# EasyArduino_2025-08-07.net
KiCad netlist of a schematic drawn in EasyEDA Pro
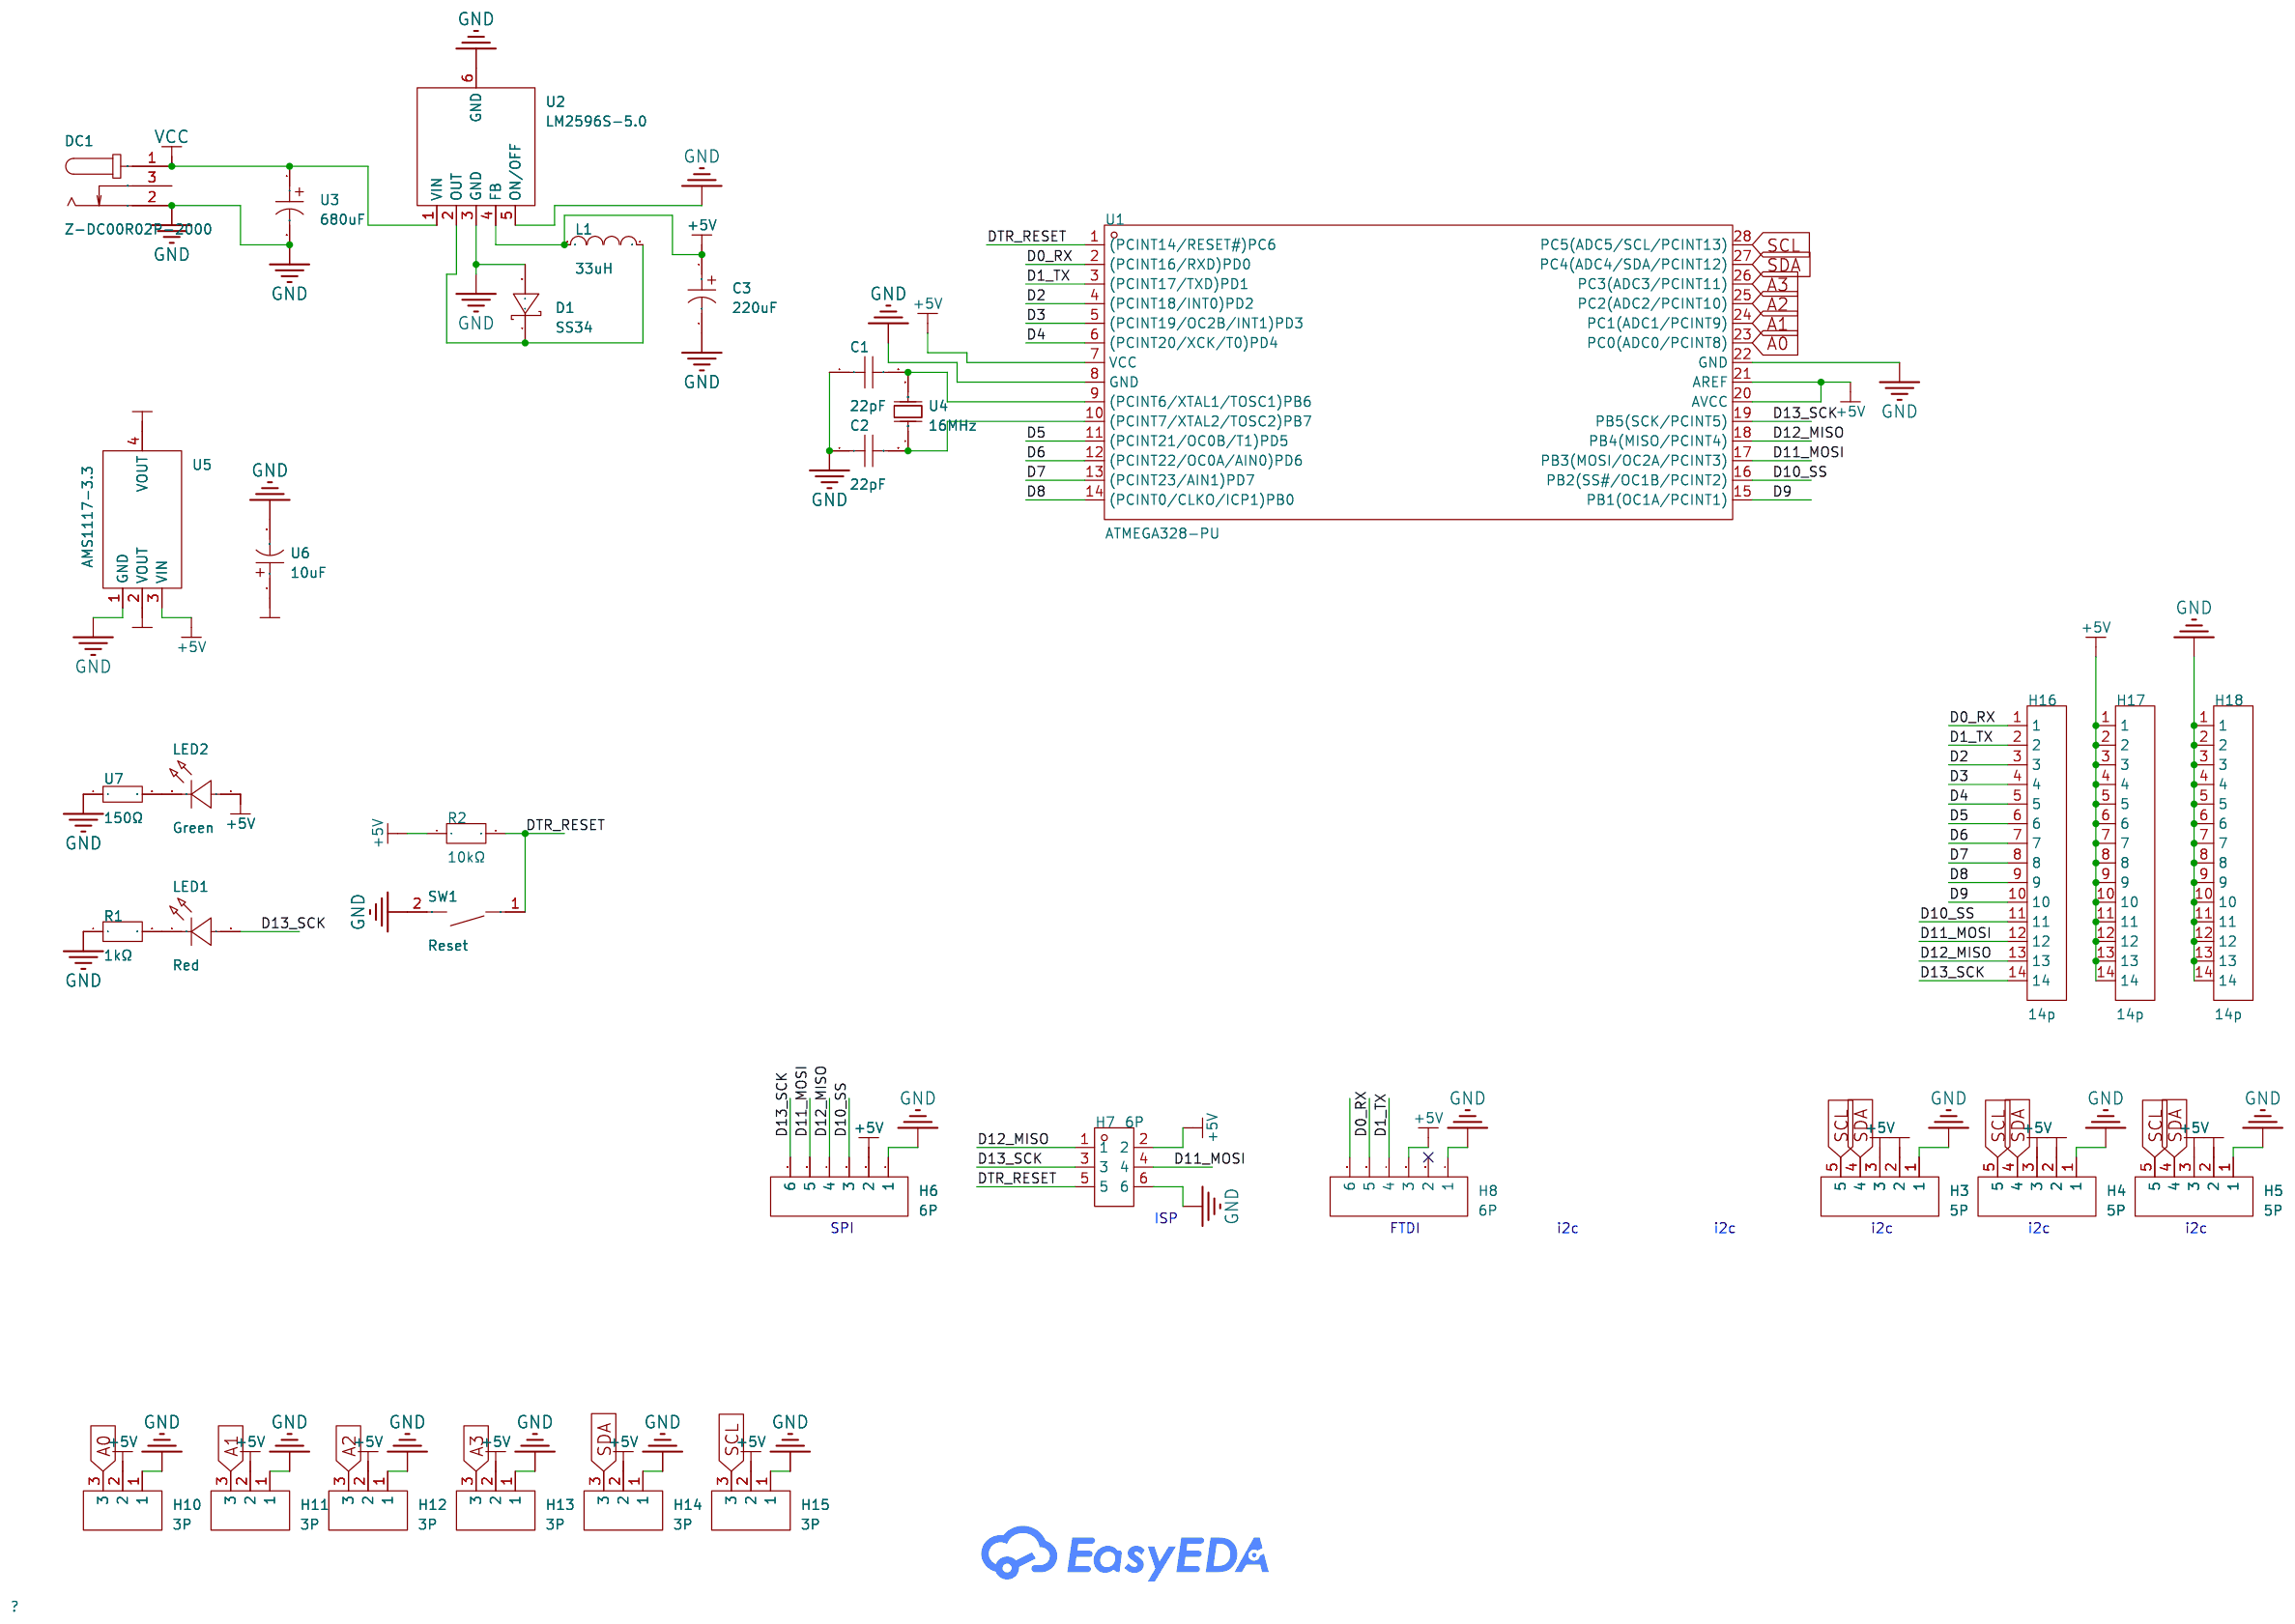
[diagram p0: schematic sheet]

(export (version "E")
  (design (tool "Eeschema 10.0.6"))
  (components
    (comp (ref "C1")
      (value "22pF")
      (footprint "easyedapro:CAP-TH_L4.0-W2.6-P2.50-D0.5")
      (description "Capacitance:22pF Tolerance:±5% Tolerance:±5% Voltage Rating:50V Temperature Coefficient:C0G")
      (fields (field (name "Manufacturer Part") "K220J15C0GF5TL2") (field (name "Manufacturer") "VISHAY(威世)"))
      (libsource (lib "easyedapro") (part "K220J15C0GF5TL2"))
    )
    (comp (ref "C2")
      (value "22pF")
      (footprint "easyedapro:CAP-TH_L4.0-W2.6-P2.50-D0.5")
      (description "Capacitance:22pF Tolerance:±5% Tolerance:±5% Voltage Rating:50V Temperature Coefficient:C0G")
      (fields (field (name "Manufacturer Part") "K220J15C0GF5TL2") (field (name "Manufacturer") "VISHAY(威世)"))
      (libsource (lib "easyedapro") (part "K220J15C0GF5TL2"))
    )
    (comp (ref "C3")
      (value "220uF")
      (footprint "easyedapro:CAP-SMD_BD6.3-L6.6-W6.6-FD")
      (fields (field (name "Manufacturer Part") "189RV0063") (field (name "Manufacturer") "KNSCHA(科尼盛)"))
      (libsource (lib "easyedapro") (part "189RV0063"))
    )
    (comp (ref "D1")
      (value "SS34")
      (footprint "easyedapro:SMA_L4.4-W2.8-LS5.4-RD")
      (description "Forward Voltage (Vf@If):500mV@3A Reverse Voltage (Vr):40V Average Rectified Current (Io):3A")
      (libsource (lib "easyedapro") (part "SS34_C142458"))
    )
    (comp (ref "DC1")
      (value "Z-DC00R02P-2000")
      (footprint "easyedapro:DC-IN-TH_DC005")
      (fields (field (name "Manufacturer") "Ckmtw(灿科盟)"))
      (libsource (lib "easyedapro") (part "dc-005 5.5-2.0"))
    )
    (comp (ref "H3")
      (value "5P")
      (footprint "easyedapro:HDR-TH_5P-P2.54-V-M")
      (fields (field (name "Manufacturer") "XFCN(兴飞)"))
      (libsource (lib "easyedapro") (part "PZ254V-11-05P"))
    )
    (comp (ref "H4")
      (value "5P")
      (footprint "easyedapro:HDR-TH_5P-P2.54-V-M")
      (fields (field (name "Manufacturer") "XFCN(兴飞)"))
      (libsource (lib "easyedapro") (part "PZ254V-11-05P"))
    )
    (comp (ref "H5")
      (value "5P")
      (footprint "easyedapro:HDR-TH_5P-P2.54-V-M")
      (fields (field (name "Manufacturer") "XFCN(兴飞)"))
      (libsource (lib "easyedapro") (part "PZ254V-11-05P"))
    )
    (comp (ref "H6")
      (value "6P")
      (footprint "easyedapro:HDR-TH_6P-P2.54-V-M-1")
      (fields (field (name "Manufacturer") "BOOMELE(博穆精密)"))
      (libsource (lib "easyedapro") (part "Header-Male-2.54_1x6"))
    )
    (comp (ref "H7")
      (value "6P")
      (footprint "easyedapro:HDR-TH_6P-P2.54-V-M-R2-C3-S2.54")
      (fields (field (name "Manufacturer") "XFCN(兴飞)"))
      (libsource (lib "easyedapro") (part "PZ254V-12-6P"))
    )
    (comp (ref "H8")
      (value "6P")
      (footprint "easyedapro:HDR-TH_6P-P2.54-V-M-1")
      (fields (field (name "Manufacturer") "BOOMELE(博穆精密)"))
      (libsource (lib "easyedapro") (part "Header-Male-2.54_1x6"))
    )
    (comp (ref "H10")
      (value "3P")
      (footprint "easyedapro:HDR-TH_3P-P2.54-V-M")
      (fields (field (name "Manufacturer") "XFCN(兴飞)"))
      (libsource (lib "easyedapro") (part "PZ254V-11-03P_C2937625"))
    )
    (comp (ref "H11")
      (value "3P")
      (footprint "easyedapro:HDR-TH_3P-P2.54-V-M")
      (fields (field (name "Manufacturer") "XFCN(兴飞)"))
      (libsource (lib "easyedapro") (part "PZ254V-11-03P_C2937625"))
    )
    (comp (ref "H12")
      (value "3P")
      (footprint "easyedapro:HDR-TH_3P-P2.54-V-M")
      (fields (field (name "Manufacturer") "XFCN(兴飞)"))
      (libsource (lib "easyedapro") (part "PZ254V-11-03P_C2937625"))
    )
    (comp (ref "H13")
      (value "3P")
      (footprint "easyedapro:HDR-TH_3P-P2.54-V-M")
      (fields (field (name "Manufacturer") "XFCN(兴飞)"))
      (libsource (lib "easyedapro") (part "PZ254V-11-03P_C2937625"))
    )
    (comp (ref "H14")
      (value "3P")
      (footprint "easyedapro:HDR-TH_3P-P2.54-V-M")
      (fields (field (name "Manufacturer") "XFCN(兴飞)"))
      (libsource (lib "easyedapro") (part "PZ254V-11-03P_C2937625"))
    )
    (comp (ref "H15")
      (value "3P")
      (footprint "easyedapro:HDR-TH_3P-P2.54-V-M")
      (fields (field (name "Manufacturer") "XFCN(兴飞)"))
      (libsource (lib "easyedapro") (part "PZ254V-11-03P_C2937625"))
    )
    (comp (ref "H16")
      (value "14p")
      (footprint "easyedapro:HDR-TH_14P-P2.54-V-M")
      (fields (field (name "Manufacturer") "HCTL(华灿天禄)"))
      (libsource (lib "easyedapro") (part "PZ254-1-14-Z-8.5"))
    )
    (comp (ref "H17")
      (value "14p")
      (footprint "easyedapro:HDR-TH_14P-P2.54-V-M")
      (fields (field (name "Manufacturer") "HCTL(华灿天禄)"))
      (libsource (lib "easyedapro") (part "PZ254-1-14-Z-8.5"))
    )
    (comp (ref "H18")
      (value "14p")
      (footprint "easyedapro:HDR-TH_14P-P2.54-V-M")
      (fields (field (name "Manufacturer") "HCTL(华灿天禄)"))
      (libsource (lib "easyedapro") (part "PZ254-1-14-Z-8.5"))
    )
    (comp (ref "L1")
      (value "33uH")
      (footprint "easyedapro:IND-SMD_L12.3-W12.3")
      (fields (field (name "Manufacturer Part") "SMDRI127-330MT") (field (name "Manufacturer") "SXN(顺翔诺)"))
      (libsource (lib "easyedapro") (part "SMDRI127-330MT"))
    )
    (comp (ref "LED1")
      (value "Red")
      (footprint "easyedapro:LED-TH_BD3.8-P2.54-RD")
      (fields (field (name "Manufacturer") "XINGLIGHT(成兴光)"))
      (libsource (lib "easyedapro") (part "XL-302SURD"))
    )
    (comp (ref "LED2")
      (value "Green")
      (footprint "easyedapro:LED-TH_BD3.8-P2.54-FD_GREEN")
      (fields (field (name "Manufacturer") "XINGLIGHT(成兴光)"))
      (libsource (lib "easyedapro") (part "XL-302UGD"))
    )
    (comp (ref "R1")
      (value "1kΩ")
      (footprint "easyedapro:RES-TH_BD2.7-L6.2-P10.20-D0.4")
      (fields (field (name "Manufacturer Part") "MF1/4W-1K±1%-ST52") (field (name "Manufacturer") "VO(翔胜)"))
      (libsource (lib "easyedapro") (part "MF1/4W-1K±1%-ST52"))
    )
    (comp (ref "R2")
      (value "10kΩ")
      (footprint "easyedapro:RES-TH_BD2.4-L6.3-P10.30-D0.6")
      (fields
        (field (name "Manufacturer Part") "RN1/4W10KFT/BA1")
        (field (name "Manufacturer") "Tyohm(幸亚电阻)")
      )
      (libsource (lib "easyedapro") (part "RN 1/4W 10K F T/B A1"))
    )
    (comp (ref "SW1")
      (value "Reset")
      (footprint "easyedapro:SW-SMD_L3.9-W3.0-P4.45")
      (fields (field (name "Manufacturer") "XUNPU(讯普)"))
      (libsource (lib "easyedapro") (part "TS-1088-AR02016"))
    )
    (comp (ref "U1")
      (value "ATMEGA328-PU")
      (footprint "easyedapro:DIP-28_L35.0-W6.5-P2.54-LS7.6-BL")
      (fields (field (name "Manufacturer") "MICROCHIP(美国微芯)"))
      (libsource (lib "easyedapro") (part "ATMEGA328-PU"))
    )
    (comp (ref "U2")
      (value "LM2596S-5.0")
      (footprint "easyedapro:TO-263-5_L10.2-W8.6-P1.70-LS14.4-BR")
      (fields (field (name "Manufacturer") "GR(国睿)"))
      (libsource (lib "easyedapro") (part "LM2596S-5.0_C19631823"))
    )
    (comp (ref "U3")
      (value "680uF")
      (footprint "easyedapro:CAP-SMD_BD10.0-L10.3-W10.3-LS11.6-FD")
      (fields (field (name "Manufacturer Part") "RVT1E681M1010") (field (name "Manufacturer") "ROQANG(容强)"))
      (libsource (lib "easyedapro") (part "RVT1E681M1010_C5221838"))
    )
    (comp (ref "U4")
      (value "16MHz")
      (footprint "easyedapro:HC-49US_L11.0-W4.6-P4.88")
      (fields (field (name "Manufacturer Part") "49SAC16000222060") (field (name "Manufacturer") "JGHC(晶光华)"))
      (libsource (lib "easyedapro") (part "49SAC16000222060"))
    )
    (comp (ref "U5")
      (value "AMS1117-3.3")
      (footprint "easyedapro:SOT-223-3_L6.5-W3.4-P2.30-LS7.0-BR")
      (fields (field (name "Manufacturer") "AMS"))
      (libsource (lib "easyedapro") (part "AMS1117-3.3"))
    )
    (comp (ref "U6")
      (value "10uF")
      (footprint "easyedapro:CAP-SMD_BD4.0-L4.3-W4.3-FD-LS4.8")
      (fields
        (field (name "Manufacturer Part") "UUQ1A100MCL1GB")
        (field (name "Manufacturer") "Nichicon(尼吉康)")
      )
      (libsource (lib "easyedapro") (part "UUQ1A100MCL1GB"))
    )
    (comp (ref "U7")
      (value "150Ω")
      (footprint "easyedapro:RES-TH_BD2.7-L6.2-P10.20-D0.4")
      (fields (field (name "Manufacturer Part") "KNP1WS-150Ω±5%-XT52") (field (name "Manufacturer") "VO(翔胜)"))
      (libsource (lib "easyedapro") (part "KNP1WS-150Ω±5%-XT52"))
    )
  )
  (nets
    (net (code "1") (name "+3.3") (class "Default")
      (node (ref "H3") (pin "2") (pinfunction "2_2") (pintype "unspecified"))
      (node (ref "H4") (pin "2") (pinfunction "2_2") (pintype "unspecified"))
      (node (ref "H5") (pin "2") (pinfunction "2_2") (pintype "unspecified"))
      (node (ref "U5") (pin "2") (pinfunction "VOUT_2") (pintype "unspecified"))
      (node (ref "U5") (pin "4") (pinfunction "VOUT_4") (pintype "unspecified"))
      (node (ref "U6") (pin "1") (pinfunction "1_1") (pintype "input"))
    )
    (net (code "2") (name "+5V") (class "Default")
      (node (ref "C3") (pin "1") (pinfunction "1_1") (pintype "input"))
      (node (ref "H10") (pin "2") (pinfunction "2_2") (pintype "unspecified"))
      (node (ref "H11") (pin "2") (pinfunction "2_2") (pintype "unspecified"))
      (node (ref "H12") (pin "2") (pinfunction "2_2") (pintype "unspecified"))
      (node (ref "H13") (pin "2") (pinfunction "2_2") (pintype "unspecified"))
      (node (ref "H14") (pin "2") (pinfunction "2_2") (pintype "unspecified"))
      (node (ref "H15") (pin "2") (pinfunction "2_2") (pintype "unspecified"))
      (node (ref "H17") (pin "1") (pinfunction "1_1") (pintype "unspecified"))
      (node (ref "H17") (pin "10") (pinfunction "10_10") (pintype "unspecified"))
      (node (ref "H17") (pin "11") (pinfunction "11_11") (pintype "unspecified"))
      (node (ref "H17") (pin "12") (pinfunction "12_12") (pintype "unspecified"))
      (node (ref "H17") (pin "13") (pinfunction "13_13") (pintype "unspecified"))
      (node (ref "H17") (pin "14") (pinfunction "14_14") (pintype "unspecified"))
      (node (ref "H17") (pin "2") (pinfunction "2_2") (pintype "unspecified"))
      (node (ref "H17") (pin "3") (pinfunction "3_3") (pintype "unspecified"))
      (node (ref "H17") (pin "4") (pinfunction "4_4") (pintype "unspecified"))
      (node (ref "H17") (pin "5") (pinfunction "5_5") (pintype "unspecified"))
      (node (ref "H17") (pin "6") (pinfunction "6_6") (pintype "unspecified"))
      (node (ref "H17") (pin "7") (pinfunction "7_7") (pintype "unspecified"))
      (node (ref "H17") (pin "8") (pinfunction "8_8") (pintype "unspecified"))
      (node (ref "H17") (pin "9") (pinfunction "9_9") (pintype "unspecified"))
      (node (ref "H3") (pin "3") (pinfunction "3_3") (pintype "unspecified"))
      (node (ref "H4") (pin "3") (pinfunction "3_3") (pintype "unspecified"))
      (node (ref "H5") (pin "3") (pinfunction "3_3") (pintype "unspecified"))
      (node (ref "H6") (pin "2") (pinfunction "2_2") (pintype "input"))
      (node (ref "H7") (pin "2") (pinfunction "2_2") (pintype "unspecified"))
      (node (ref "H8") (pin "3") (pinfunction "3_3") (pintype "input"))
      (node (ref "L1") (pin "1") (pinfunction "1_1") (pintype "unspecified"))
      (node (ref "LED2") (pin "1") (pinfunction "A_1") (pintype "unspecified"))
      (node (ref "R2") (pin "1") (pinfunction "1_1") (pintype "unspecified"))
      (node (ref "U1") (pin "20") (pinfunction "AVCC_20") (pintype "unspecified"))
      (node (ref "U1") (pin "21") (pinfunction "AREF_21") (pintype "unspecified"))
      (node (ref "U1") (pin "7") (pinfunction "VCC_7") (pintype "unspecified"))
      (node (ref "U2") (pin "4") (pinfunction "FB_4") (pintype "unspecified"))
      (node (ref "U5") (pin "3") (pinfunction "VIN_3") (pintype "unspecified"))
    )
    (net (code "3") (name "/D0_RX") (class "Default")
      (node (ref "H16") (pin "1") (pinfunction "1_1") (pintype "unspecified"))
      (node (ref "H8") (pin "5") (pinfunction "5_5") (pintype "input"))
      (node (ref "U1") (pin "2") (pinfunction "(PCINT16/RXD)PD0_2") (pintype "unspecified"))
    )
    (net (code "4") (name "/D1_TX") (class "Default")
      (node (ref "H16") (pin "2") (pinfunction "2_2") (pintype "unspecified"))
      (node (ref "H8") (pin "4") (pinfunction "4_4") (pintype "input"))
      (node (ref "U1") (pin "3") (pinfunction "(PCINT17/TXD)PD1_3") (pintype "unspecified"))
    )
    (net (code "5") (name "/D2") (class "Default")
      (node (ref "H16") (pin "3") (pinfunction "3_3") (pintype "unspecified"))
      (node (ref "U1") (pin "4") (pinfunction "(PCINT18/INT0)PD2_4") (pintype "unspecified"))
    )
    (net (code "6") (name "/D3") (class "Default")
      (node (ref "H16") (pin "4") (pinfunction "4_4") (pintype "unspecified"))
      (node (ref "U1") (pin "5") (pinfunction "(PCINT19/OC2B/INT1)PD3_5") (pintype "unspecified"))
    )
    (net (code "7") (name "/D4") (class "Default")
      (node (ref "H16") (pin "5") (pinfunction "5_5") (pintype "unspecified"))
      (node (ref "U1") (pin "6") (pinfunction "(PCINT20/XCK/T0)PD4_6") (pintype "unspecified"))
    )
    (net (code "8") (name "/D5") (class "Default")
      (node (ref "H16") (pin "6") (pinfunction "6_6") (pintype "unspecified"))
      (node (ref "U1") (pin "11") (pinfunction "(PCINT21/OC0B/T1)PD5_11") (pintype "unspecified"))
    )
    (net (code "9") (name "/D6") (class "Default")
      (node (ref "H16") (pin "7") (pinfunction "7_7") (pintype "unspecified"))
      (node (ref "U1") (pin "12") (pinfunction "(PCINT22/OC0A/AIN0)PD6_12") (pintype "unspecified"))
    )
    (net (code "10") (name "/D7") (class "Default")
      (node (ref "H16") (pin "8") (pinfunction "8_8") (pintype "unspecified"))
      (node (ref "U1") (pin "13") (pinfunction "(PCINT23/AIN1)PD7_13") (pintype "unspecified"))
    )
    (net (code "11") (name "/D8") (class "Default")
      (node (ref "H16") (pin "9") (pinfunction "9_9") (pintype "unspecified"))
      (node (ref "U1") (pin "14") (pinfunction "(PCINT0/CLKO/ICP1)PB0_14") (pintype "unspecified"))
    )
    (net (code "12") (name "/D9") (class "Default")
      (node (ref "H16") (pin "10") (pinfunction "10_10") (pintype "unspecified"))
      (node (ref "U1") (pin "15") (pinfunction "PB1(OC1A/PCINT1)_15") (pintype "unspecified"))
    )
    (net (code "13") (name "/D10_SS") (class "Default")
      (node (ref "H16") (pin "11") (pinfunction "11_11") (pintype "unspecified"))
      (node (ref "H6") (pin "3") (pinfunction "3_3") (pintype "input"))
      (node (ref "U1") (pin "16") (pinfunction "PB2(SS#/OC1B/PCINT2)_16") (pintype "unspecified"))
    )
    (net (code "14") (name "/D11_MOSI") (class "Default")
      (node (ref "H16") (pin "12") (pinfunction "12_12") (pintype "unspecified"))
      (node (ref "H6") (pin "5") (pinfunction "5_5") (pintype "input"))
      (node (ref "H7") (pin "4") (pinfunction "4_4") (pintype "unspecified"))
      (node (ref "U1") (pin "17") (pinfunction "PB3(MOSI/OC2A/PCINT3)_17") (pintype "unspecified"))
    )
    (net (code "15") (name "/D12_MISO") (class "Default")
      (node (ref "H16") (pin "13") (pinfunction "13_13") (pintype "unspecified"))
      (node (ref "H6") (pin "4") (pinfunction "4_4") (pintype "input"))
      (node (ref "H7") (pin "1") (pinfunction "1_1") (pintype "unspecified"))
      (node (ref "U1") (pin "18") (pinfunction "PB4(MISO/PCINT4)_18") (pintype "unspecified"))
    )
    (net (code "16") (name "/D13_SCK") (class "Default")
      (node (ref "H16") (pin "14") (pinfunction "14_14") (pintype "unspecified"))
      (node (ref "H6") (pin "6") (pinfunction "6_6") (pintype "input"))
      (node (ref "H7") (pin "3") (pinfunction "3_3") (pintype "unspecified"))
      (node (ref "LED1") (pin "2") (pinfunction "A_2") (pintype "unspecified"))
      (node (ref "U1") (pin "19") (pinfunction "PB5(SCK/PCINT5)_19") (pintype "unspecified"))
    )
    (net (code "17") (name "/DTR_RESET") (class "Default")
      (node (ref "H7") (pin "5") (pinfunction "5_5") (pintype "unspecified"))
      (node (ref "R2") (pin "2") (pinfunction "2_2") (pintype "unspecified"))
      (node (ref "SW1") (pin "1") (pinfunction "1_1") (pintype "unspecified"))
      (node (ref "U1") (pin "1") (pinfunction "(PCINT14/RESET#)PC6_1") (pintype "unspecified"))
    )
    (net (code "18") (name "A0") (class "Default")
      (node (ref "H10") (pin "3") (pinfunction "3_3") (pintype "unspecified"))
      (node (ref "U1") (pin "23") (pinfunction "PC0(ADC0/PCINT8)_23") (pintype "unspecified"))
    )
    (net (code "19") (name "A1") (class "Default")
      (node (ref "H11") (pin "3") (pinfunction "3_3") (pintype "unspecified"))
      (node (ref "U1") (pin "24") (pinfunction "PC1(ADC1/PCINT9)_24") (pintype "unspecified"))
    )
    (net (code "20") (name "A2") (class "Default")
      (node (ref "H12") (pin "3") (pinfunction "3_3") (pintype "unspecified"))
      (node (ref "U1") (pin "25") (pinfunction "PC2(ADC2/PCINT10)_25") (pintype "unspecified"))
    )
    (net (code "21") (name "A3") (class "Default")
      (node (ref "H13") (pin "3") (pinfunction "3_3") (pintype "unspecified"))
      (node (ref "U1") (pin "26") (pinfunction "PC3(ADC3/PCINT11)_26") (pintype "unspecified"))
    )
    (net (code "22") (name "GND") (class "Default")
      (node (ref "C1") (pin "1") (pinfunction "1_1") (pintype "unspecified"))
      (node (ref "C2") (pin "1") (pinfunction "1_1") (pintype "unspecified"))
      (node (ref "C3") (pin "2") (pinfunction "2_2") (pintype "input"))
      (node (ref "D1") (pin "2") (pinfunction "A_2") (pintype "input"))
      (node (ref "DC1") (pin "2") (pinfunction "2_2") (pintype "unspecified"))
      (node (ref "H10") (pin "1") (pinfunction "1_1") (pintype "unspecified"))
      (node (ref "H11") (pin "1") (pinfunction "1_1") (pintype "unspecified"))
      (node (ref "H12") (pin "1") (pinfunction "1_1") (pintype "unspecified"))
      (node (ref "H13") (pin "1") (pinfunction "1_1") (pintype "unspecified"))
      (node (ref "H14") (pin "1") (pinfunction "1_1") (pintype "unspecified"))
      (node (ref "H15") (pin "1") (pinfunction "1_1") (pintype "unspecified"))
      (node (ref "H18") (pin "1") (pinfunction "1_1") (pintype "unspecified"))
      (node (ref "H18") (pin "10") (pinfunction "10_10") (pintype "unspecified"))
      (node (ref "H18") (pin "11") (pinfunction "11_11") (pintype "unspecified"))
      (node (ref "H18") (pin "12") (pinfunction "12_12") (pintype "unspecified"))
      (node (ref "H18") (pin "13") (pinfunction "13_13") (pintype "unspecified"))
      (node (ref "H18") (pin "14") (pinfunction "14_14") (pintype "unspecified"))
      (node (ref "H18") (pin "2") (pinfunction "2_2") (pintype "unspecified"))
      (node (ref "H18") (pin "3") (pinfunction "3_3") (pintype "unspecified"))
      (node (ref "H18") (pin "4") (pinfunction "4_4") (pintype "unspecified"))
      (node (ref "H18") (pin "5") (pinfunction "5_5") (pintype "unspecified"))
      (node (ref "H18") (pin "6") (pinfunction "6_6") (pintype "unspecified"))
      (node (ref "H18") (pin "7") (pinfunction "7_7") (pintype "unspecified"))
      (node (ref "H18") (pin "8") (pinfunction "8_8") (pintype "unspecified"))
      (node (ref "H18") (pin "9") (pinfunction "9_9") (pintype "unspecified"))
      (node (ref "H3") (pin "1") (pinfunction "1_1") (pintype "unspecified"))
      (node (ref "H4") (pin "1") (pinfunction "1_1") (pintype "unspecified"))
      (node (ref "H5") (pin "1") (pinfunction "1_1") (pintype "unspecified"))
      (node (ref "H6") (pin "1") (pinfunction "1_1") (pintype "input"))
      (node (ref "H7") (pin "6") (pinfunction "6_6") (pintype "unspecified"))
      (node (ref "H8") (pin "1") (pinfunction "1_1") (pintype "input"))
      (node (ref "R1") (pin "1") (pinfunction "1_1") (pintype "unspecified"))
      (node (ref "SW1") (pin "2") (pinfunction "2_2") (pintype "unspecified"))
      (node (ref "U1") (pin "22") (pinfunction "GND_22") (pintype "unspecified"))
      (node (ref "U1") (pin "8") (pinfunction "GND_8") (pintype "unspecified"))
      (node (ref "U2") (pin "3") (pinfunction "GND_3") (pintype "unspecified"))
      (node (ref "U2") (pin "5") (pinfunction "ON/OFF_5") (pintype "unspecified"))
      (node (ref "U2") (pin "6") (pinfunction "GND_6") (pintype "unspecified"))
      (node (ref "U3") (pin "2") (pinfunction "2_2") (pintype "input"))
      (node (ref "U5") (pin "1") (pinfunction "GND_1") (pintype "unspecified"))
      (node (ref "U6") (pin "2") (pinfunction "2_2") (pintype "input"))
      (node (ref "U7") (pin "1") (pinfunction "1_1") (pintype "unspecified"))
    )
    (net (code "23") (name "Net-(D1-K)") (class "Default")
      (node (ref "D1") (pin "1") (pinfunction "K_1") (pintype "input"))
      (node (ref "L1") (pin "2") (pinfunction "2_2") (pintype "unspecified"))
      (node (ref "U2") (pin "2") (pinfunction "OUT_2") (pintype "unspecified"))
    )
    (net (code "24") (name "Net-(LED1-K)") (class "Default")
      (node (ref "LED1") (pin "1") (pinfunction "K_1") (pintype "unspecified"))
      (node (ref "R1") (pin "2") (pinfunction "2_2") (pintype "unspecified"))
    )
    (net (code "25") (name "Net-(LED2-K)") (class "Default")
      (node (ref "LED2") (pin "2") (pinfunction "K_2") (pintype "unspecified"))
      (node (ref "U7") (pin "2") (pinfunction "2_2") (pintype "unspecified"))
    )
    (net (code "26") (name "Net-(U1-(PCINT6{slash}XTAL1{slash}TOSC1)PB6)") (class "Default")
      (node (ref "C1") (pin "2") (pinfunction "2_2") (pintype "unspecified"))
      (node (ref "U1") (pin "9") (pinfunction "(PCINT6/XTAL1/TOSC1)PB6_9") (pintype "unspecified"))
      (node (ref "U4") (pin "2") (pinfunction "OSC2_2") (pintype "input"))
    )
    (net (code "27") (name "Net-(U1-(PCINT7{slash}XTAL2{slash}TOSC2)PB7)") (class "Default")
      (node (ref "C2") (pin "2") (pinfunction "2_2") (pintype "unspecified"))
      (node (ref "U1") (pin "10") (pinfunction "(PCINT7/XTAL2/TOSC2)PB7_10") (pintype "unspecified"))
      (node (ref "U4") (pin "1") (pinfunction "OSC1_1") (pintype "input"))
    )
    (net (code "28") (name "SCL") (class "Default")
      (node (ref "H15") (pin "3") (pinfunction "3_3") (pintype "unspecified"))
      (node (ref "H3") (pin "5") (pinfunction "5_5") (pintype "unspecified"))
      (node (ref "H4") (pin "5") (pinfunction "5_5") (pintype "unspecified"))
      (node (ref "H5") (pin "5") (pinfunction "5_5") (pintype "unspecified"))
      (node (ref "U1") (pin "28") (pinfunction "PC5(ADC5/SCL/PCINT13)_28") (pintype "unspecified"))
    )
    (net (code "29") (name "SDA") (class "Default")
      (node (ref "H14") (pin "3") (pinfunction "3_3") (pintype "unspecified"))
      (node (ref "H3") (pin "4") (pinfunction "4_4") (pintype "unspecified"))
      (node (ref "H4") (pin "4") (pinfunction "4_4") (pintype "unspecified"))
      (node (ref "H5") (pin "4") (pinfunction "4_4") (pintype "unspecified"))
      (node (ref "U1") (pin "27") (pinfunction "PC4(ADC4/SDA/PCINT12)_27") (pintype "unspecified"))
    )
    (net (code "30") (name "VCC") (class "Default")
      (node (ref "DC1") (pin "1") (pinfunction "1_1") (pintype "unspecified"))
      (node (ref "U2") (pin "1") (pinfunction "VIN_1") (pintype "unspecified"))
      (node (ref "U3") (pin "1") (pinfunction "1_1") (pintype "input"))
    )
    (net (code "31") (name "unconnected-(DC1-Pad3)") (class "Default")
      (node (ref "DC1") (pin "3") (pinfunction "3_3") (pintype "unspecified"))
    )
    (net (code "32") (name "unconnected-(H8-Pad2)") (class "Default")
      (node (ref "H8") (pin "2") (pinfunction "2_2") (pintype "input+no_connect"))
    )
    (net (code "33") (name "unconnected-(H8-Pad6)") (class "Default")
      (node (ref "H8") (pin "6") (pinfunction "6_6") (pintype "input"))
    )
  )
)
